# EmonTxShieldV2_5_simple.net
KiCad netlist of a schematic drawn in EAGLE
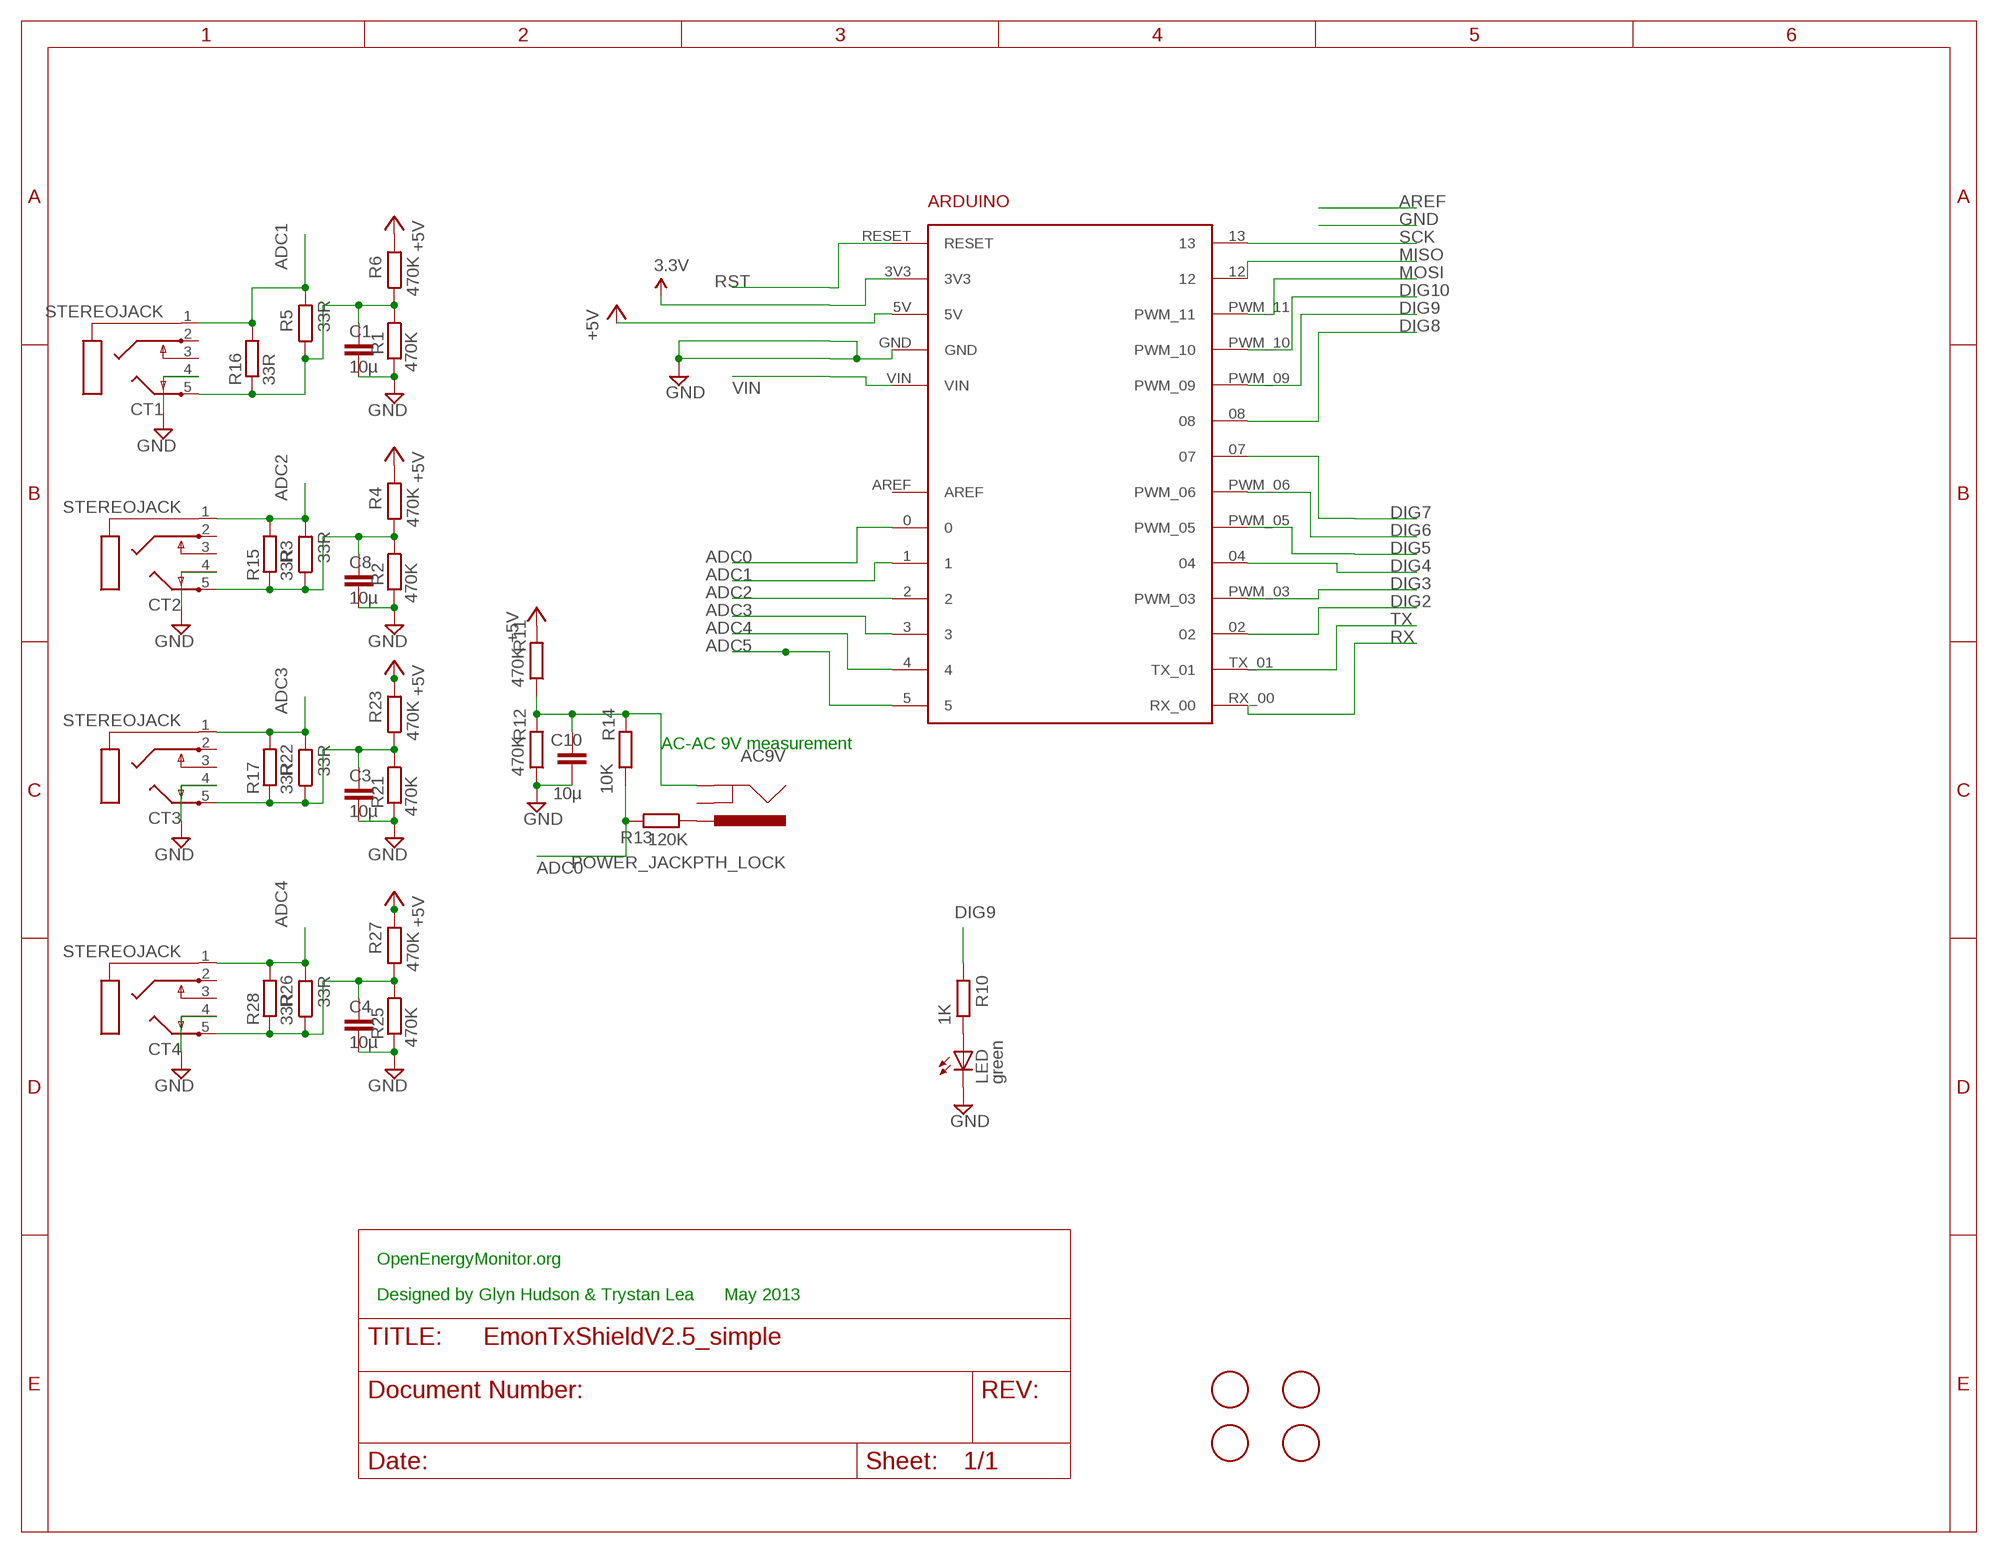
[diagram p0: schematic, sheet 1]

(export (version "E")
  (design (tool "Eeschema 10.0.6"))
  (components
    (comp (ref "AC9V")
      (value "POWER_JACKPTH_LOCK")
      (footprint "eagle-import:POWER_JACK_PTH_LOCK")
      (libsource (lib "eagle-import") (part "POWER_JACKPTH_LOCK"))
    )
    (comp (ref "ARDUINO1")
      (value "ARDUINO2")
      (footprint "eagle-import:ARDUINO2")
      (libsource (lib "eagle-import") (part "ARDUINO2"))
    )
    (comp (ref "C1")
      (value "10µ")
      (footprint "eagle-import:C0603")
      (libsource (lib "eagle-import") (part "C-EUC0603"))
    )
    (comp (ref "C3")
      (value "10µ")
      (footprint "eagle-import:C0603")
      (libsource (lib "eagle-import") (part "C-EUC0603"))
    )
    (comp (ref "C4")
      (value "10µ")
      (footprint "eagle-import:C0603")
      (libsource (lib "eagle-import") (part "C-EUC0603"))
    )
    (comp (ref "C8")
      (value "10µ")
      (footprint "eagle-import:C0603")
      (libsource (lib "eagle-import") (part "C-EUC0603"))
    )
    (comp (ref "C10")
      (value "10µ")
      (footprint "eagle-import:C0603")
      (libsource (lib "eagle-import") (part "C-EUC0603"))
    )
    (comp (ref "CT1")
      (value "STEREOJACK")
      (footprint "eagle-import:STX3100")
      (libsource (lib "eagle-import") (part "STEREOJACK"))
    )
    (comp (ref "CT2")
      (value "STEREOJACK")
      (footprint "eagle-import:STX3100")
      (libsource (lib "eagle-import") (part "STEREOJACK"))
    )
    (comp (ref "CT3")
      (value "STEREOJACK")
      (footprint "eagle-import:STX3100")
      (libsource (lib "eagle-import") (part "STEREOJACK"))
    )
    (comp (ref "CT4")
      (value "STEREOJACK")
      (footprint "eagle-import:STX3100")
      (libsource (lib "eagle-import") (part "STEREOJACK"))
    )
    (comp (ref "LED")
      (value "green")
      (footprint "eagle-import:CHIPLED_0805")
      (libsource (lib "eagle-import") (part "LEDCHIPLED_0805"))
    )
    (comp (ref "R1")
      (value "470K")
      (footprint "eagle-import:R0603")
      (libsource (lib "eagle-import") (part "R-EU_R0603"))
    )
    (comp (ref "R2")
      (value "470K")
      (footprint "eagle-import:R0603")
      (libsource (lib "eagle-import") (part "R-EU_R0603"))
    )
    (comp (ref "R3")
      (value "33R")
      (footprint "eagle-import:0204_7")
      (libsource (lib "eagle-import") (part "R-EU_0204/7"))
    )
    (comp (ref "R4")
      (value "470K")
      (footprint "eagle-import:R0603")
      (libsource (lib "eagle-import") (part "R-EU_R0603"))
    )
    (comp (ref "R5")
      (value "33R")
      (footprint "eagle-import:0204_7")
      (libsource (lib "eagle-import") (part "R-EU_0204/7"))
    )
    (comp (ref "R6")
      (value "470K")
      (footprint "eagle-import:R0603")
      (libsource (lib "eagle-import") (part "R-EU_R0603"))
    )
    (comp (ref "R10")
      (value "1K")
      (footprint "eagle-import:R0603")
      (libsource (lib "eagle-import") (part "R-EU_R0603"))
    )
    (comp (ref "R11")
      (value "470K")
      (footprint "eagle-import:R0603")
      (libsource (lib "eagle-import") (part "R-EU_R0603"))
    )
    (comp (ref "R12")
      (value "470K")
      (footprint "eagle-import:R0603")
      (libsource (lib "eagle-import") (part "R-EU_R0603"))
    )
    (comp (ref "R13")
      (value "120K")
      (footprint "eagle-import:R0603")
      (libsource (lib "eagle-import") (part "R-EU_R0603"))
    )
    (comp (ref "R14")
      (value "10K")
      (footprint "eagle-import:R0603")
      (libsource (lib "eagle-import") (part "R-EU_R0603"))
    )
    (comp (ref "R15")
      (value "33R")
      (footprint "eagle-import:R1206")
      (libsource (lib "eagle-import") (part "R-EU_R1206"))
    )
    (comp (ref "R16")
      (value "33R")
      (footprint "eagle-import:R1206")
      (libsource (lib "eagle-import") (part "R-EU_R1206"))
    )
    (comp (ref "R17")
      (value "33R")
      (footprint "eagle-import:R1206")
      (libsource (lib "eagle-import") (part "R-EU_R1206"))
    )
    (comp (ref "R21")
      (value "470K")
      (footprint "eagle-import:R0603")
      (libsource (lib "eagle-import") (part "R-EU_R0603"))
    )
    (comp (ref "R22")
      (value "33R")
      (footprint "eagle-import:0204_7")
      (libsource (lib "eagle-import") (part "R-EU_0204/7"))
    )
    (comp (ref "R23")
      (value "470K")
      (footprint "eagle-import:R0603")
      (libsource (lib "eagle-import") (part "R-EU_R0603"))
    )
    (comp (ref "R25")
      (value "470K")
      (footprint "eagle-import:R0603")
      (libsource (lib "eagle-import") (part "R-EU_R0603"))
    )
    (comp (ref "R26")
      (value "33R")
      (footprint "eagle-import:0204_7")
      (libsource (lib "eagle-import") (part "R-EU_0204/7"))
    )
    (comp (ref "R27")
      (value "470K")
      (footprint "eagle-import:R0603")
      (libsource (lib "eagle-import") (part "R-EU_R0603"))
    )
    (comp (ref "R28")
      (value "33R")
      (footprint "eagle-import:R1206")
      (libsource (lib "eagle-import") (part "R-EU_R1206"))
    )
    (comp (ref "U$1")
      (value "FIDUCIAL")
      (footprint "eagle-import:FIDUCIAL_1MM")
      (libsource (lib "eagle-import") (part "FIDUCIAL"))
    )
    (comp (ref "U$3")
      (value "FIDUCIAL")
      (footprint "eagle-import:FIDUCIAL_1MM")
      (libsource (lib "eagle-import") (part "FIDUCIAL"))
    )
    (comp (ref "U$4")
      (value "FIDUCIAL")
      (footprint "eagle-import:FIDUCIAL_1MM")
      (libsource (lib "eagle-import") (part "FIDUCIAL"))
    )
    (comp (ref "U$5")
      (value "FIDUCIAL")
      (footprint "eagle-import:FIDUCIAL_1MM")
      (libsource (lib "eagle-import") (part "FIDUCIAL"))
    )
  )
  (nets
    (net (code "1") (name "+5V") (class "Default")
      (node (ref "ARDUINO1") (pin "5V") (pinfunction "5V_5V") (pintype "bidirectional"))
      (node (ref "R11") (pin "2") (pinfunction "2_2") (pintype "passive"))
      (node (ref "R23") (pin "2") (pinfunction "2_2") (pintype "passive"))
      (node (ref "R27") (pin "2") (pinfunction "2_2") (pintype "passive"))
      (node (ref "R4") (pin "2") (pinfunction "2_2") (pintype "passive"))
      (node (ref "R6") (pin "2") (pinfunction "2_2") (pintype "passive"))
    )
    (net (code "2") (name "/ADC0") (class "Default")
      (node (ref "ARDUINO1") (pin "0") (pinfunction "0_0") (pintype "bidirectional"))
      (node (ref "R13") (pin "2") (pinfunction "2_2") (pintype "passive"))
      (node (ref "R14") (pin "1") (pinfunction "1_1") (pintype "passive"))
    )
    (net (code "3") (name "/ADC1") (class "Default")
      (node (ref "ARDUINO1") (pin "1") (pinfunction "1_1") (pintype "bidirectional"))
      (node (ref "CT1") (pin "1") (pinfunction "1_1") (pintype "passive"))
      (node (ref "R16") (pin "2") (pinfunction "2_2") (pintype "passive"))
      (node (ref "R5") (pin "2") (pinfunction "2_2") (pintype "passive"))
    )
    (net (code "4") (name "/ADC2") (class "Default")
      (node (ref "ARDUINO1") (pin "2") (pinfunction "2_2") (pintype "bidirectional"))
      (node (ref "CT2") (pin "1") (pinfunction "1_1") (pintype "passive"))
      (node (ref "R15") (pin "2") (pinfunction "2_2") (pintype "passive"))
      (node (ref "R3") (pin "2") (pinfunction "2_2") (pintype "passive"))
    )
    (net (code "5") (name "/ADC3") (class "Default")
      (node (ref "ARDUINO1") (pin "3") (pinfunction "3_3") (pintype "bidirectional"))
      (node (ref "CT3") (pin "1") (pinfunction "1_1") (pintype "passive"))
      (node (ref "R17") (pin "2") (pinfunction "2_2") (pintype "passive"))
      (node (ref "R22") (pin "2") (pinfunction "2_2") (pintype "passive"))
    )
    (net (code "6") (name "/ADC4") (class "Default")
      (node (ref "ARDUINO1") (pin "4") (pinfunction "4_4") (pintype "bidirectional"))
      (node (ref "CT4") (pin "1") (pinfunction "1_1") (pintype "passive"))
      (node (ref "R26") (pin "2") (pinfunction "2_2") (pintype "passive"))
      (node (ref "R28") (pin "2") (pinfunction "2_2") (pintype "passive"))
    )
    (net (code "7") (name "/ADC5") (class "Default")
      (node (ref "ARDUINO1") (pin "5") (pinfunction "5_5") (pintype "bidirectional"))
    )
    (net (code "9") (name "/DIG2") (class "Default")
      (node (ref "ARDUINO1") (pin "02") (pinfunction "02_02") (pintype "bidirectional"))
    )
    (net (code "10") (name "/DIG3") (class "Default")
      (node (ref "ARDUINO1") (pin "PWM_03") (pinfunction "PWM_03_PWM_03") (pintype "bidirectional"))
    )
    (net (code "11") (name "/DIG4") (class "Default")
      (node (ref "ARDUINO1") (pin "04") (pinfunction "04_04") (pintype "bidirectional"))
    )
    (net (code "12") (name "/DIG5") (class "Default")
      (node (ref "ARDUINO1") (pin "PWM_05") (pinfunction "PWM_05_PWM_05") (pintype "bidirectional"))
    )
    (net (code "13") (name "/DIG6") (class "Default")
      (node (ref "ARDUINO1") (pin "PWM_06") (pinfunction "PWM_06_PWM_06") (pintype "bidirectional"))
    )
    (net (code "14") (name "/DIG7") (class "Default")
      (node (ref "ARDUINO1") (pin "07") (pinfunction "07_07") (pintype "bidirectional"))
    )
    (net (code "15") (name "/DIG8") (class "Default")
      (node (ref "ARDUINO1") (pin "08") (pinfunction "08_08") (pintype "bidirectional"))
    )
    (net (code "16") (name "/DIG9") (class "Default")
      (node (ref "ARDUINO1") (pin "PWM_09") (pinfunction "PWM_09_PWM_09") (pintype "bidirectional"))
      (node (ref "R10") (pin "2") (pinfunction "2_2") (pintype "passive"))
    )
    (net (code "17") (name "/DIG10") (class "Default")
      (node (ref "ARDUINO1") (pin "PWM_10") (pinfunction "PWM_10_PWM_10") (pintype "bidirectional"))
    )
    (net (code "18") (name "/MISO") (class "Default")
      (node (ref "ARDUINO1") (pin "12") (pinfunction "12_12") (pintype "bidirectional"))
    )
    (net (code "19") (name "/MOSI") (class "Default")
      (node (ref "ARDUINO1") (pin "PWM_11") (pinfunction "PWM_11_PWM_11") (pintype "bidirectional"))
    )
    (net (code "20") (name "/RST") (class "Default")
      (node (ref "ARDUINO1") (pin "RESET") (pinfunction "RESET_RESET") (pintype "bidirectional"))
    )
    (net (code "21") (name "/RX") (class "Default")
      (node (ref "ARDUINO1") (pin "RX_00") (pinfunction "RX_00_RX_00") (pintype "bidirectional"))
    )
    (net (code "22") (name "/SCK") (class "Default")
      (node (ref "ARDUINO1") (pin "13") (pinfunction "13_13") (pintype "bidirectional"))
    )
    (net (code "23") (name "/TX") (class "Default")
      (node (ref "ARDUINO1") (pin "TX_01") (pinfunction "TX_01_TX_01") (pintype "bidirectional"))
    )
    (net (code "24") (name "/VIN") (class "Default")
      (node (ref "ARDUINO1") (pin "VIN") (pinfunction "VIN_VIN") (pintype "bidirectional"))
    )
    (net (code "25") (name "3.3V") (class "Default")
      (node (ref "ARDUINO1") (pin "3V3") (pinfunction "3V3_3V3") (pintype "bidirectional"))
    )
    (net (code "26") (name "GND") (class "Default")
      (node (ref "ARDUINO1") (pin "GND") (pinfunction "GND_GND") (pintype "bidirectional"))
      (node (ref "C1") (pin "2") (pinfunction "2_2") (pintype "passive"))
      (node (ref "C10") (pin "2") (pinfunction "2_2") (pintype "passive"))
      (node (ref "C3") (pin "2") (pinfunction "2_2") (pintype "passive"))
      (node (ref "C4") (pin "2") (pinfunction "2_2") (pintype "passive"))
      (node (ref "C8") (pin "2") (pinfunction "2_2") (pintype "passive"))
      (node (ref "CT1") (pin "4") (pinfunction "4_4") (pintype "passive"))
      (node (ref "CT2") (pin "4") (pinfunction "4_4") (pintype "passive"))
      (node (ref "CT3") (pin "4") (pinfunction "4_4") (pintype "passive"))
      (node (ref "CT4") (pin "4") (pinfunction "4_4") (pintype "passive"))
      (node (ref "LED") (pin "C") (pinfunction "C_C") (pintype "passive"))
      (node (ref "R1") (pin "2") (pinfunction "2_2") (pintype "passive"))
      (node (ref "R12") (pin "1") (pinfunction "1_1") (pintype "passive"))
      (node (ref "R2") (pin "2") (pinfunction "2_2") (pintype "passive"))
      (node (ref "R21") (pin "2") (pinfunction "2_2") (pintype "passive"))
      (node (ref "R25") (pin "2") (pinfunction "2_2") (pintype "passive"))
    )
    (net (code "27") (name "Net-(AC9V-PadGND)") (class "Default")
      (node (ref "AC9V") (pin "GND") (pinfunction "GND_GND") (pintype "bidirectional"))
      (node (ref "C10") (pin "1") (pinfunction "1_1") (pintype "passive"))
      (node (ref "R11") (pin "1") (pinfunction "1_1") (pintype "passive"))
      (node (ref "R12") (pin "2") (pinfunction "2_2") (pintype "passive"))
      (node (ref "R14") (pin "2") (pinfunction "2_2") (pintype "passive"))
    )
    (net (code "28") (name "Net-(AC9V-PadPWR)") (class "Default")
      (node (ref "AC9V") (pin "PWR") (pinfunction "PWR_PWR") (pintype "bidirectional"))
      (node (ref "R13") (pin "1") (pinfunction "1_1") (pintype "passive"))
    )
    (net (code "29") (name "Net-(C1-Pad1)") (class "Default")
      (node (ref "C1") (pin "1") (pinfunction "1_1") (pintype "passive"))
      (node (ref "CT1") (pin "5") (pinfunction "5_5") (pintype "passive"))
      (node (ref "R1") (pin "1") (pinfunction "1_1") (pintype "passive"))
      (node (ref "R16") (pin "1") (pinfunction "1_1") (pintype "passive"))
      (node (ref "R5") (pin "1") (pinfunction "1_1") (pintype "passive"))
      (node (ref "R6") (pin "1") (pinfunction "1_1") (pintype "passive"))
    )
    (net (code "30") (name "Net-(C3-Pad1)") (class "Default")
      (node (ref "C3") (pin "1") (pinfunction "1_1") (pintype "passive"))
      (node (ref "CT3") (pin "5") (pinfunction "5_5") (pintype "passive"))
      (node (ref "R17") (pin "1") (pinfunction "1_1") (pintype "passive"))
      (node (ref "R21") (pin "1") (pinfunction "1_1") (pintype "passive"))
      (node (ref "R22") (pin "1") (pinfunction "1_1") (pintype "passive"))
      (node (ref "R23") (pin "1") (pinfunction "1_1") (pintype "passive"))
    )
    (net (code "31") (name "Net-(C4-Pad1)") (class "Default")
      (node (ref "C4") (pin "1") (pinfunction "1_1") (pintype "passive"))
      (node (ref "CT4") (pin "5") (pinfunction "5_5") (pintype "passive"))
      (node (ref "R25") (pin "1") (pinfunction "1_1") (pintype "passive"))
      (node (ref "R26") (pin "1") (pinfunction "1_1") (pintype "passive"))
      (node (ref "R27") (pin "1") (pinfunction "1_1") (pintype "passive"))
      (node (ref "R28") (pin "1") (pinfunction "1_1") (pintype "passive"))
    )
    (net (code "32") (name "Net-(C8-Pad1)") (class "Default")
      (node (ref "C8") (pin "1") (pinfunction "1_1") (pintype "passive"))
      (node (ref "CT2") (pin "5") (pinfunction "5_5") (pintype "passive"))
      (node (ref "R15") (pin "1") (pinfunction "1_1") (pintype "passive"))
      (node (ref "R2") (pin "1") (pinfunction "1_1") (pintype "passive"))
      (node (ref "R3") (pin "1") (pinfunction "1_1") (pintype "passive"))
      (node (ref "R4") (pin "1") (pinfunction "1_1") (pintype "passive"))
    )
    (net (code "33") (name "Net-(LED-PadA)") (class "Default")
      (node (ref "LED") (pin "A") (pinfunction "A_A") (pintype "passive"))
      (node (ref "R10") (pin "1") (pinfunction "1_1") (pintype "passive"))
    )
    (net (code "34") (name "unconnected-(AC9V-PadGNDBREAK)") (class "Default")
      (node (ref "AC9V") (pin "GNDBREAK") (pinfunction "GNDBREAK_GNDBREAK") (pintype "bidirectional"))
    )
    (net (code "35") (name "unconnected-(ARDUINO1-PadAREF)") (class "Default")
      (node (ref "ARDUINO1") (pin "AREF") (pinfunction "AREF_AREF") (pintype "bidirectional"))
    )
    (net (code "36") (name "unconnected-(CT1-Pad2)") (class "Default")
      (node (ref "CT1") (pin "2") (pinfunction "2_2") (pintype "passive"))
    )
    (net (code "37") (name "unconnected-(CT1-Pad3)") (class "Default")
      (node (ref "CT1") (pin "3") (pinfunction "3_3") (pintype "passive"))
    )
    (net (code "38") (name "unconnected-(CT2-Pad2)") (class "Default")
      (node (ref "CT2") (pin "2") (pinfunction "2_2") (pintype "passive"))
    )
    (net (code "39") (name "unconnected-(CT2-Pad3)") (class "Default")
      (node (ref "CT2") (pin "3") (pinfunction "3_3") (pintype "passive"))
    )
    (net (code "40") (name "unconnected-(CT3-Pad2)") (class "Default")
      (node (ref "CT3") (pin "2") (pinfunction "2_2") (pintype "passive"))
    )
    (net (code "41") (name "unconnected-(CT3-Pad3)") (class "Default")
      (node (ref "CT3") (pin "3") (pinfunction "3_3") (pintype "passive"))
    )
    (net (code "42") (name "unconnected-(CT4-Pad2)") (class "Default")
      (node (ref "CT4") (pin "2") (pinfunction "2_2") (pintype "passive"))
    )
    (net (code "43") (name "unconnected-(CT4-Pad3)") (class "Default")
      (node (ref "CT4") (pin "3") (pinfunction "3_3") (pintype "passive"))
    )
  )
)
